# ADC_connections.net
KiCad netlist of a schematic drawn in Altium Designer
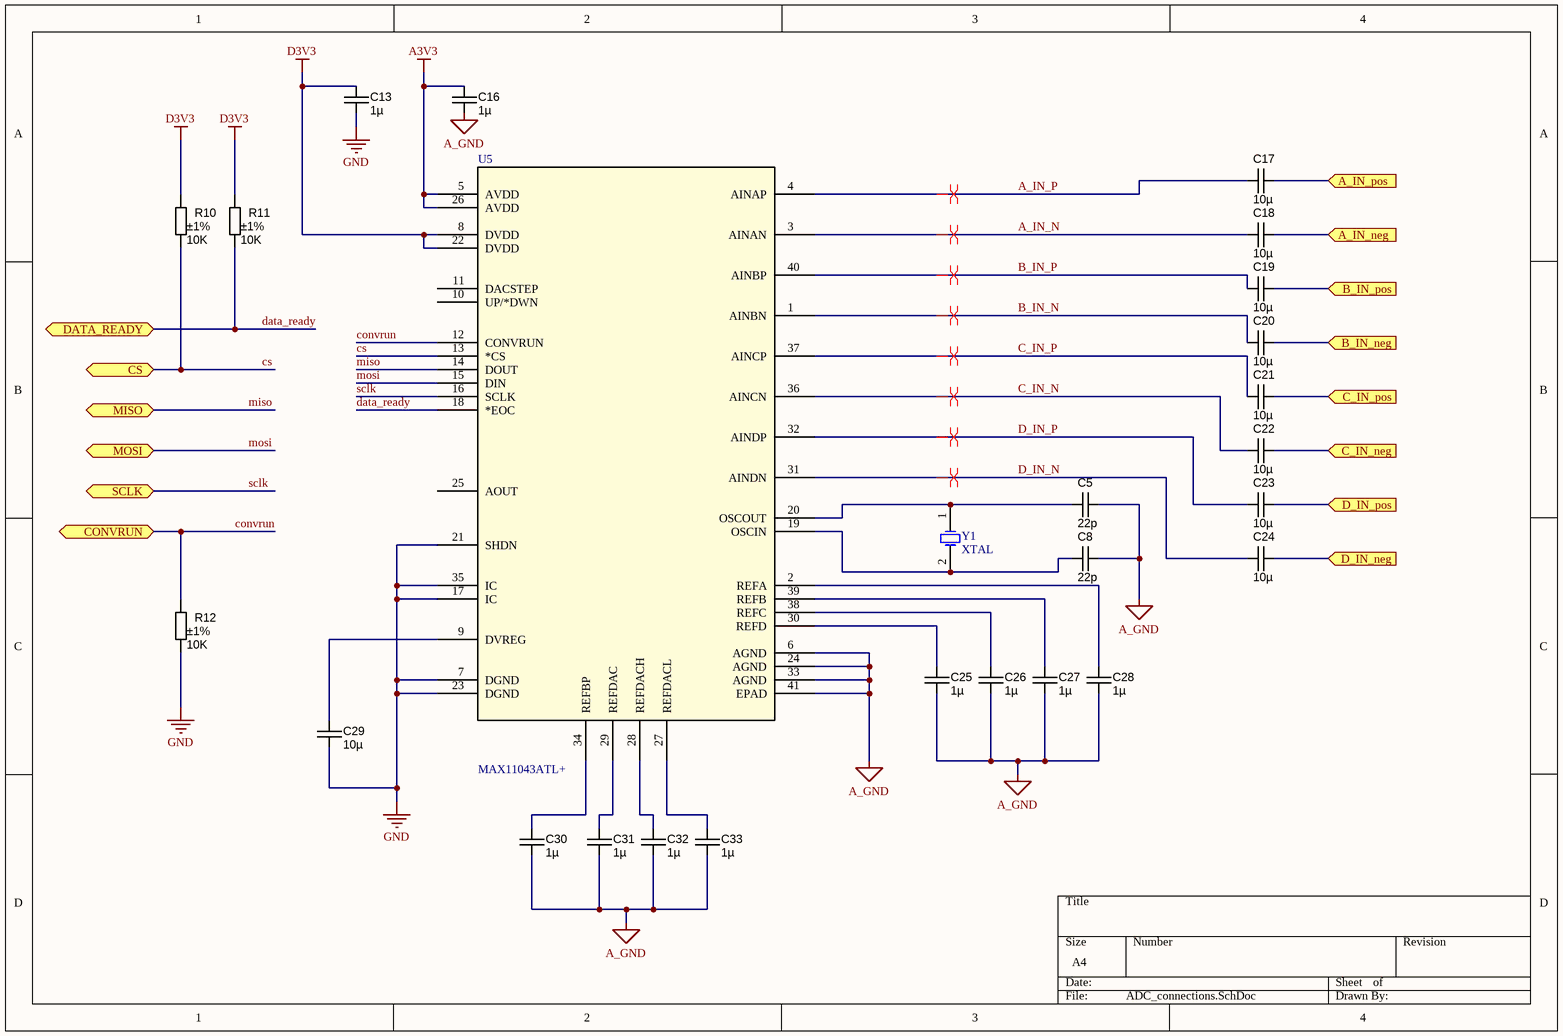
[diagram p0: ADC_connections.SchDoc]

(export (version "E")
  (design (tool "Eeschema 10.0.6"))
  (components
    (comp (ref "C5")
      (value "22p")
      (footprint "CAPC2012X135N")
      (description "Capacitor SMD Cer 22pF 5% 50V NP0 0805")
      (fields (field (name "TOLERANCE") "±5%") (field (name "Comment") "approved sub OK"))
      (libsource (lib "PBL - Capacitors") (part "CAPC_27p_0805_NP0_50V_5%"))
    )
    (comp (ref "C8")
      (value "22p")
      (footprint "CAPC2012X135N")
      (description "Capacitor SMD Cer 22pF 5% 50V NP0 0805")
      (fields (field (name "TOLERANCE") "±5%") (field (name "Comment") "approved sub OK"))
      (libsource (lib "PBL - Capacitors") (part "CAPC_27p_0805_NP0_50V_5%"))
    )
    (comp (ref "C13")
      (value "1µ")
      (footprint "CAPC2012X135N")
      (description "Capacitor SMD Cer 1uF 10% 16V X7R 0805")
      (fields (field (name "TOLERANCE") "±10%") (field (name "Comment") "approved sub OK"))
      (libsource (lib "PBL - Capacitors") (part "CAPC_1u_0805_X7R_16V_10%"))
    )
    (comp (ref "C16")
      (value "1µ")
      (footprint "CAPC2012X135N")
      (description "Capacitor SMD Cer 1uF 10% 16V X7R 0805")
      (fields (field (name "TOLERANCE") "±10%") (field (name "Comment") "approved sub OK"))
      (libsource (lib "PBL - Capacitors") (part "CAPC_1u_0805_X7R_16V_10%"))
    )
    (comp (ref "C17")
      (value "10µ")
      (footprint "CAPC2012X135N")
      (description "Capacitor SMD Cer 10uF 10% 10V X5R 0805")
      (fields (field (name "TOLERANCE") "±10%") (field (name "Comment") "approved sub OK"))
      (libsource (lib "PBL - Capacitors") (part "CAPC_10u_0805_10V"))
    )
    (comp (ref "C18")
      (value "10µ")
      (footprint "CAPC2012X135N")
      (description "Capacitor SMD Cer 10uF 10% 10V X5R 0805")
      (fields (field (name "TOLERANCE") "±10%") (field (name "Comment") "approved sub OK"))
      (libsource (lib "PBL - Capacitors") (part "CAPC_10u_0805_10V"))
    )
    (comp (ref "C19")
      (value "10µ")
      (footprint "CAPC2012X135N")
      (description "Capacitor SMD Cer 10uF 10% 10V X5R 0805")
      (fields (field (name "TOLERANCE") "±10%") (field (name "Comment") "approved sub OK"))
      (libsource (lib "PBL - Capacitors") (part "CAPC_10u_0805_10V"))
    )
    (comp (ref "C20")
      (value "10µ")
      (footprint "CAPC2012X135N")
      (description "Capacitor SMD Cer 10uF 10% 10V X5R 0805")
      (fields (field (name "TOLERANCE") "±10%") (field (name "Comment") "approved sub OK"))
      (libsource (lib "PBL - Capacitors") (part "CAPC_10u_0805_10V"))
    )
    (comp (ref "C21")
      (value "10µ")
      (footprint "CAPC2012X135N")
      (description "Capacitor SMD Cer 10uF 10% 10V X5R 0805")
      (fields (field (name "TOLERANCE") "±10%") (field (name "Comment") "approved sub OK"))
      (libsource (lib "PBL - Capacitors") (part "CAPC_10u_0805_10V"))
    )
    (comp (ref "C22")
      (value "10µ")
      (footprint "CAPC2012X135N")
      (description "Capacitor SMD Cer 10uF 10% 10V X5R 0805")
      (fields (field (name "TOLERANCE") "±10%") (field (name "Comment") "approved sub OK"))
      (libsource (lib "PBL - Capacitors") (part "CAPC_10u_0805_10V"))
    )
    (comp (ref "C23")
      (value "10µ")
      (footprint "CAPC2012X135N")
      (description "Capacitor SMD Cer 10uF 10% 10V X5R 0805")
      (fields (field (name "TOLERANCE") "±10%") (field (name "Comment") "approved sub OK"))
      (libsource (lib "PBL - Capacitors") (part "CAPC_10u_0805_10V"))
    )
    (comp (ref "C24")
      (value "10µ")
      (footprint "CAPC2012X135N")
      (description "Capacitor SMD Cer 10uF 10% 10V X5R 0805")
      (fields (field (name "TOLERANCE") "±10%") (field (name "Comment") "approved sub OK"))
      (libsource (lib "PBL - Capacitors") (part "CAPC_10u_0805_10V"))
    )
    (comp (ref "C25")
      (value "1µ")
      (footprint "CAPC2012X135N")
      (description "Capacitor SMD Cer 1uF 10% 16V X7R 0805")
      (fields (field (name "TOLERANCE") "±10%") (field (name "Comment") "approved sub OK"))
      (libsource (lib "PBL - Capacitors") (part "CAPC_1u_0805_X7R_16V_10%"))
    )
    (comp (ref "C26")
      (value "1µ")
      (footprint "CAPC2012X135N")
      (description "Capacitor SMD Cer 1uF 10% 16V X7R 0805")
      (fields (field (name "TOLERANCE") "±10%") (field (name "Comment") "approved sub OK"))
      (libsource (lib "PBL - Capacitors") (part "CAPC_1u_0805_X7R_16V_10%"))
    )
    (comp (ref "C27")
      (value "1µ")
      (footprint "CAPC2012X135N")
      (description "Capacitor SMD Cer 1uF 10% 16V X7R 0805")
      (fields (field (name "TOLERANCE") "±10%") (field (name "Comment") "approved sub OK"))
      (libsource (lib "PBL - Capacitors") (part "CAPC_1u_0805_X7R_16V_10%"))
    )
    (comp (ref "C28")
      (value "1µ")
      (footprint "CAPC2012X135N")
      (description "Capacitor SMD Cer 1uF 10% 16V X7R 0805")
      (fields (field (name "TOLERANCE") "±10%") (field (name "Comment") "approved sub OK"))
      (libsource (lib "PBL - Capacitors") (part "CAPC_1u_0805_X7R_16V_10%"))
    )
    (comp (ref "C29")
      (value "10µ")
      (footprint "CAPC2012X135N")
      (description "Capacitor SMD Cer 10uF 10% 10V X5R 0805")
      (fields (field (name "TOLERANCE") "±10%") (field (name "Comment") "approved sub OK"))
      (libsource (lib "PBL - Capacitors") (part "CAPC_10u_0805_10V"))
    )
    (comp (ref "C30")
      (value "1µ")
      (footprint "CAPC2012X135N")
      (description "Capacitor SMD Cer 1uF 10% 16V X7R 0805")
      (fields (field (name "TOLERANCE") "±10%") (field (name "Comment") "approved sub OK"))
      (libsource (lib "PBL - Capacitors") (part "CAPC_1u_0805_X7R_16V_10%"))
    )
    (comp (ref "C31")
      (value "1µ")
      (footprint "CAPC2012X135N")
      (description "Capacitor SMD Cer 1uF 10% 16V X7R 0805")
      (fields (field (name "TOLERANCE") "±10%") (field (name "Comment") "approved sub OK"))
      (libsource (lib "PBL - Capacitors") (part "CAPC_1u_0805_X7R_16V_10%"))
    )
    (comp (ref "C32")
      (value "1µ")
      (footprint "CAPC2012X135N")
      (description "Capacitor SMD Cer 1uF 10% 16V X7R 0805")
      (fields (field (name "TOLERANCE") "±10%") (field (name "Comment") "approved sub OK"))
      (libsource (lib "PBL - Capacitors") (part "CAPC_1u_0805_X7R_16V_10%"))
    )
    (comp (ref "C33")
      (value "1µ")
      (footprint "CAPC2012X135N")
      (description "Capacitor SMD Cer 1uF 10% 16V X7R 0805")
      (fields (field (name "TOLERANCE") "±10%") (field (name "Comment") "approved sub OK"))
      (libsource (lib "PBL - Capacitors") (part "CAPC_1u_0805_X7R_16V_10%"))
    )
    (comp (ref "R10")
      (value "10K")
      (footprint "RESC2012X70N")
      (description "Resistor SMD chip 10k Ohm 0.125W 1% 0805")
      (fields (field (name "TOLERANCE") "±1%") (field (name "Comment") "Thick Film"))
      (libsource (lib "PBL - Resistors") (part "RES_10K_0805_1%"))
    )
    (comp (ref "R11")
      (value "10K")
      (footprint "RESC2012X70N")
      (description "Resistor SMD chip 10k Ohm 0.125W 1% 0805")
      (fields (field (name "TOLERANCE") "±1%") (field (name "Comment") "Thick Film"))
      (libsource (lib "PBL - Resistors") (part "RES_10K_0805_1%"))
    )
    (comp (ref "R12")
      (value "10K")
      (footprint "RESC2012X70N")
      (description "Resistor SMD chip 10k Ohm 0.125W 1% 0805")
      (fields (field (name "TOLERANCE") "±1%") (field (name "Comment") "Thick Film"))
      (libsource (lib "PBL - Resistors") (part "RES_10K_0805_1%"))
    )
    (comp (ref "U5")
      (value "MAX11043ATL+")
      (footprint "21-0141I_T4066-5")
      (description "Imported")
      (libsource (lib "AltiumDesigner") (part "MAX11043ATL+"))
    )
    (comp (ref "Y1")
      (value "XTAL")
      (footprint "Quartz Crystal HC-49USSX")
      (description "Crystal Oscillator")
      (fields (field (name "PUBLISHER") "Altium Limited"))
      (libsource (lib "Miscellaneous Devices") (part "XTAL"))
    )
  )
  (nets
    (net (code "1") (name "/A_IN_N") (class "Default")
      (node (ref "C18") (pin "2") (pintype "passive"))
      (node (ref "U5") (pin "3") (pinfunction "AINAN_3") (pintype "passive"))
    )
    (net (code "2") (name "/A_IN_P") (class "Default")
      (node (ref "C17") (pin "2") (pintype "passive"))
      (node (ref "U5") (pin "4") (pinfunction "AINAP_4") (pintype "passive"))
    )
    (net (code "3") (name "/A_IN_neg") (class "Default") (node (ref "C18") (pin "1") (pintype "passive")))
    (net (code "4") (name "/A_IN_pos") (class "Default") (node (ref "C17") (pin "1") (pintype "passive")))
    (net (code "5") (name "/B_IN_N") (class "Default")
      (node (ref "C20") (pin "2") (pintype "passive"))
      (node (ref "U5") (pin "1") (pinfunction "AINBN_1") (pintype "passive"))
    )
    (net (code "6") (name "/B_IN_P") (class "Default")
      (node (ref "C19") (pin "1") (pintype "passive"))
      (node (ref "U5") (pin "40") (pinfunction "AINBP_40") (pintype "passive"))
    )
    (net (code "7") (name "/B_IN_neg") (class "Default") (node (ref "C20") (pin "1") (pintype "passive")))
    (net (code "8") (name "/B_IN_pos") (class "Default") (node (ref "C19") (pin "2") (pintype "passive")))
    (net (code "9") (name "/C_IN_N") (class "Default")
      (node (ref "C22") (pin "1") (pintype "passive"))
      (node (ref "U5") (pin "36") (pinfunction "AINCN_36") (pintype "passive"))
    )
    (net (code "10") (name "/C_IN_P") (class "Default")
      (node (ref "C21") (pin "1") (pintype "passive"))
      (node (ref "U5") (pin "37") (pinfunction "AINCP_37") (pintype "passive"))
    )
    (net (code "11") (name "/C_IN_neg") (class "Default") (node (ref "C22") (pin "2") (pintype "passive")))
    (net (code "12") (name "/C_IN_pos") (class "Default") (node (ref "C21") (pin "2") (pintype "passive")))
    (net (code "13") (name "/D_IN_N") (class "Default")
      (node (ref "C24") (pin "1") (pintype "passive"))
      (node (ref "U5") (pin "31") (pinfunction "AINDN_31") (pintype "passive"))
    )
    (net (code "14") (name "/D_IN_P") (class "Default")
      (node (ref "C23") (pin "1") (pintype "passive"))
      (node (ref "U5") (pin "32") (pinfunction "AINDP_32") (pintype "passive"))
    )
    (net (code "15") (name "/D_IN_neg") (class "Default") (node (ref "C24") (pin "2") (pintype "passive")))
    (net (code "16") (name "/D_IN_pos") (class "Default") (node (ref "C23") (pin "2") (pintype "passive")))
    (net (code "17") (name "/convrun") (class "Default")
      (node (ref "R12") (pin "1") (pinfunction "1_1") (pintype "passive"))
      (node (ref "U5") (pin "12") (pinfunction "CONVRUN_12") (pintype "passive"))
    )
    (net (code "18") (name "/cs") (class "Default")
      (node (ref "R10") (pin "2") (pinfunction "2_2") (pintype "passive"))
      (node (ref "U5") (pin "13") (pinfunction "*CS_13") (pintype "passive"))
    )
    (net (code "19") (name "/data_ready") (class "Default")
      (node (ref "R11") (pin "2") (pinfunction "2_2") (pintype "passive"))
      (node (ref "U5") (pin "18") (pinfunction "*EOC_18") (pintype "passive"))
    )
    (net (code "20") (name "/miso") (class "Default")
      (node (ref "U5") (pin "14") (pinfunction "DOUT_14") (pintype "passive"))
    )
    (net (code "21") (name "/mosi") (class "Default")
      (node (ref "U5") (pin "15") (pinfunction "DIN_15") (pintype "passive"))
    )
    (net (code "22") (name "/sclk") (class "Default")
      (node (ref "U5") (pin "16") (pinfunction "SCLK_16") (pintype "passive"))
    )
    (net (code "23") (name "A3V3") (class "Default")
      (node (ref "C16") (pin "1") (pintype "passive"))
      (node (ref "U5") (pin "26") (pinfunction "AVDD_26") (pintype "power_in"))
      (node (ref "U5") (pin "5") (pinfunction "AVDD_5") (pintype "power_in"))
    )
    (net (code "24") (name "A_GND") (class "Default")
      (node (ref "C16") (pin "2") (pintype "passive"))
      (node (ref "C25") (pin "2") (pintype "passive"))
      (node (ref "C26") (pin "2") (pintype "passive"))
      (node (ref "C27") (pin "2") (pintype "passive"))
      (node (ref "C28") (pin "2") (pintype "passive"))
      (node (ref "C30") (pin "2") (pintype "passive"))
      (node (ref "C31") (pin "2") (pintype "passive"))
      (node (ref "C32") (pin "2") (pintype "passive"))
      (node (ref "C33") (pin "2") (pintype "passive"))
      (node (ref "C5") (pin "2") (pintype "passive"))
      (node (ref "C8") (pin "2") (pintype "passive"))
      (node (ref "U5") (pin "24") (pinfunction "AGND_24") (pintype "power_in"))
      (node (ref "U5") (pin "33") (pinfunction "AGND_33") (pintype "power_in"))
      (node (ref "U5") (pin "41") (pinfunction "EPAD_41") (pintype "passive"))
      (node (ref "U5") (pin "6") (pinfunction "AGND_6") (pintype "power_in"))
    )
    (net (code "25") (name "D3V3") (class "Default")
      (node (ref "C13") (pin "1") (pintype "passive"))
      (node (ref "R10") (pin "1") (pinfunction "1_1") (pintype "passive"))
      (node (ref "R11") (pin "1") (pinfunction "1_1") (pintype "passive"))
      (node (ref "U5") (pin "22") (pinfunction "DVDD_22") (pintype "power_in"))
      (node (ref "U5") (pin "8") (pinfunction "DVDD_8") (pintype "power_in"))
    )
    (net (code "26") (name "GND") (class "Default")
      (node (ref "C13") (pin "2") (pintype "passive"))
      (node (ref "C29") (pin "1") (pintype "passive"))
      (node (ref "R12") (pin "2") (pinfunction "2_2") (pintype "passive"))
      (node (ref "U5") (pin "17") (pinfunction "IC_17") (pintype "passive"))
      (node (ref "U5") (pin "21") (pinfunction "SHDN_21") (pintype "passive"))
      (node (ref "U5") (pin "23") (pinfunction "DGND_23") (pintype "power_in"))
      (node (ref "U5") (pin "35") (pinfunction "IC_35") (pintype "passive"))
      (node (ref "U5") (pin "7") (pinfunction "DGND_7") (pintype "power_in"))
    )
    (net (code "27") (name "Net-(U5-DVREG)") (class "Default")
      (node (ref "C29") (pin "2") (pintype "passive"))
      (node (ref "U5") (pin "9") (pinfunction "DVREG_9") (pintype "passive"))
    )
    (net (code "28") (name "Net-(U5-OSCIN)") (class "Default")
      (node (ref "C8") (pin "1") (pintype "passive"))
      (node (ref "U5") (pin "19") (pinfunction "OSCIN_19") (pintype "passive"))
      (node (ref "Y1") (pin "2") (pinfunction "OSC2_2") (pintype "passive"))
    )
    (net (code "29") (name "Net-(U5-OSCOUT)") (class "Default")
      (node (ref "C5") (pin "1") (pintype "passive"))
      (node (ref "U5") (pin "20") (pinfunction "OSCOUT_20") (pintype "passive"))
      (node (ref "Y1") (pin "1") (pinfunction "OSC1_1") (pintype "passive"))
    )
    (net (code "30") (name "Net-(U5-REFA)") (class "Default")
      (node (ref "C28") (pin "1") (pintype "passive"))
      (node (ref "U5") (pin "2") (pinfunction "REFA_2") (pintype "passive"))
    )
    (net (code "31") (name "Net-(U5-REFB)") (class "Default")
      (node (ref "C27") (pin "1") (pintype "passive"))
      (node (ref "U5") (pin "39") (pinfunction "REFB_39") (pintype "passive"))
    )
    (net (code "32") (name "Net-(U5-REFBP)") (class "Default")
      (node (ref "C30") (pin "1") (pintype "passive"))
      (node (ref "U5") (pin "34") (pinfunction "REFBP_34") (pintype "passive"))
    )
    (net (code "33") (name "Net-(U5-REFC)") (class "Default")
      (node (ref "C26") (pin "1") (pintype "passive"))
      (node (ref "U5") (pin "38") (pinfunction "REFC_38") (pintype "passive"))
    )
    (net (code "34") (name "Net-(U5-REFD)") (class "Default")
      (node (ref "C25") (pin "1") (pintype "passive"))
      (node (ref "U5") (pin "30") (pinfunction "REFD_30") (pintype "passive"))
    )
    (net (code "35") (name "Net-(U5-REFDAC)") (class "Default")
      (node (ref "C31") (pin "1") (pintype "passive"))
      (node (ref "U5") (pin "29") (pinfunction "REFDAC_29") (pintype "passive"))
    )
    (net (code "36") (name "Net-(U5-REFDACH)") (class "Default")
      (node (ref "C32") (pin "1") (pintype "passive"))
      (node (ref "U5") (pin "28") (pinfunction "REFDACH_28") (pintype "passive"))
    )
    (net (code "37") (name "Net-(U5-REFDACL)") (class "Default")
      (node (ref "C33") (pin "1") (pintype "passive"))
      (node (ref "U5") (pin "27") (pinfunction "REFDACL_27") (pintype "passive"))
    )
    (net (code "38") (name "unconnected-(U5-AOUT-Pad25)") (class "Default")
      (node (ref "U5") (pin "25") (pinfunction "AOUT_25") (pintype "passive"))
    )
    (net (code "39") (name "unconnected-(U5-DACSTEP-Pad11)") (class "Default")
      (node (ref "U5") (pin "11") (pinfunction "DACSTEP_11") (pintype "passive"))
    )
    (net (code "40") (name "unconnected-(U5-UP{slash}*DWN-Pad10)") (class "Default")
      (node (ref "U5") (pin "10") (pinfunction "UP/*DWN_10") (pintype "passive"))
    )
  )
)
